# Transmitter_schematic.net
KiCad netlist of a schematic drawn in EasyEDA
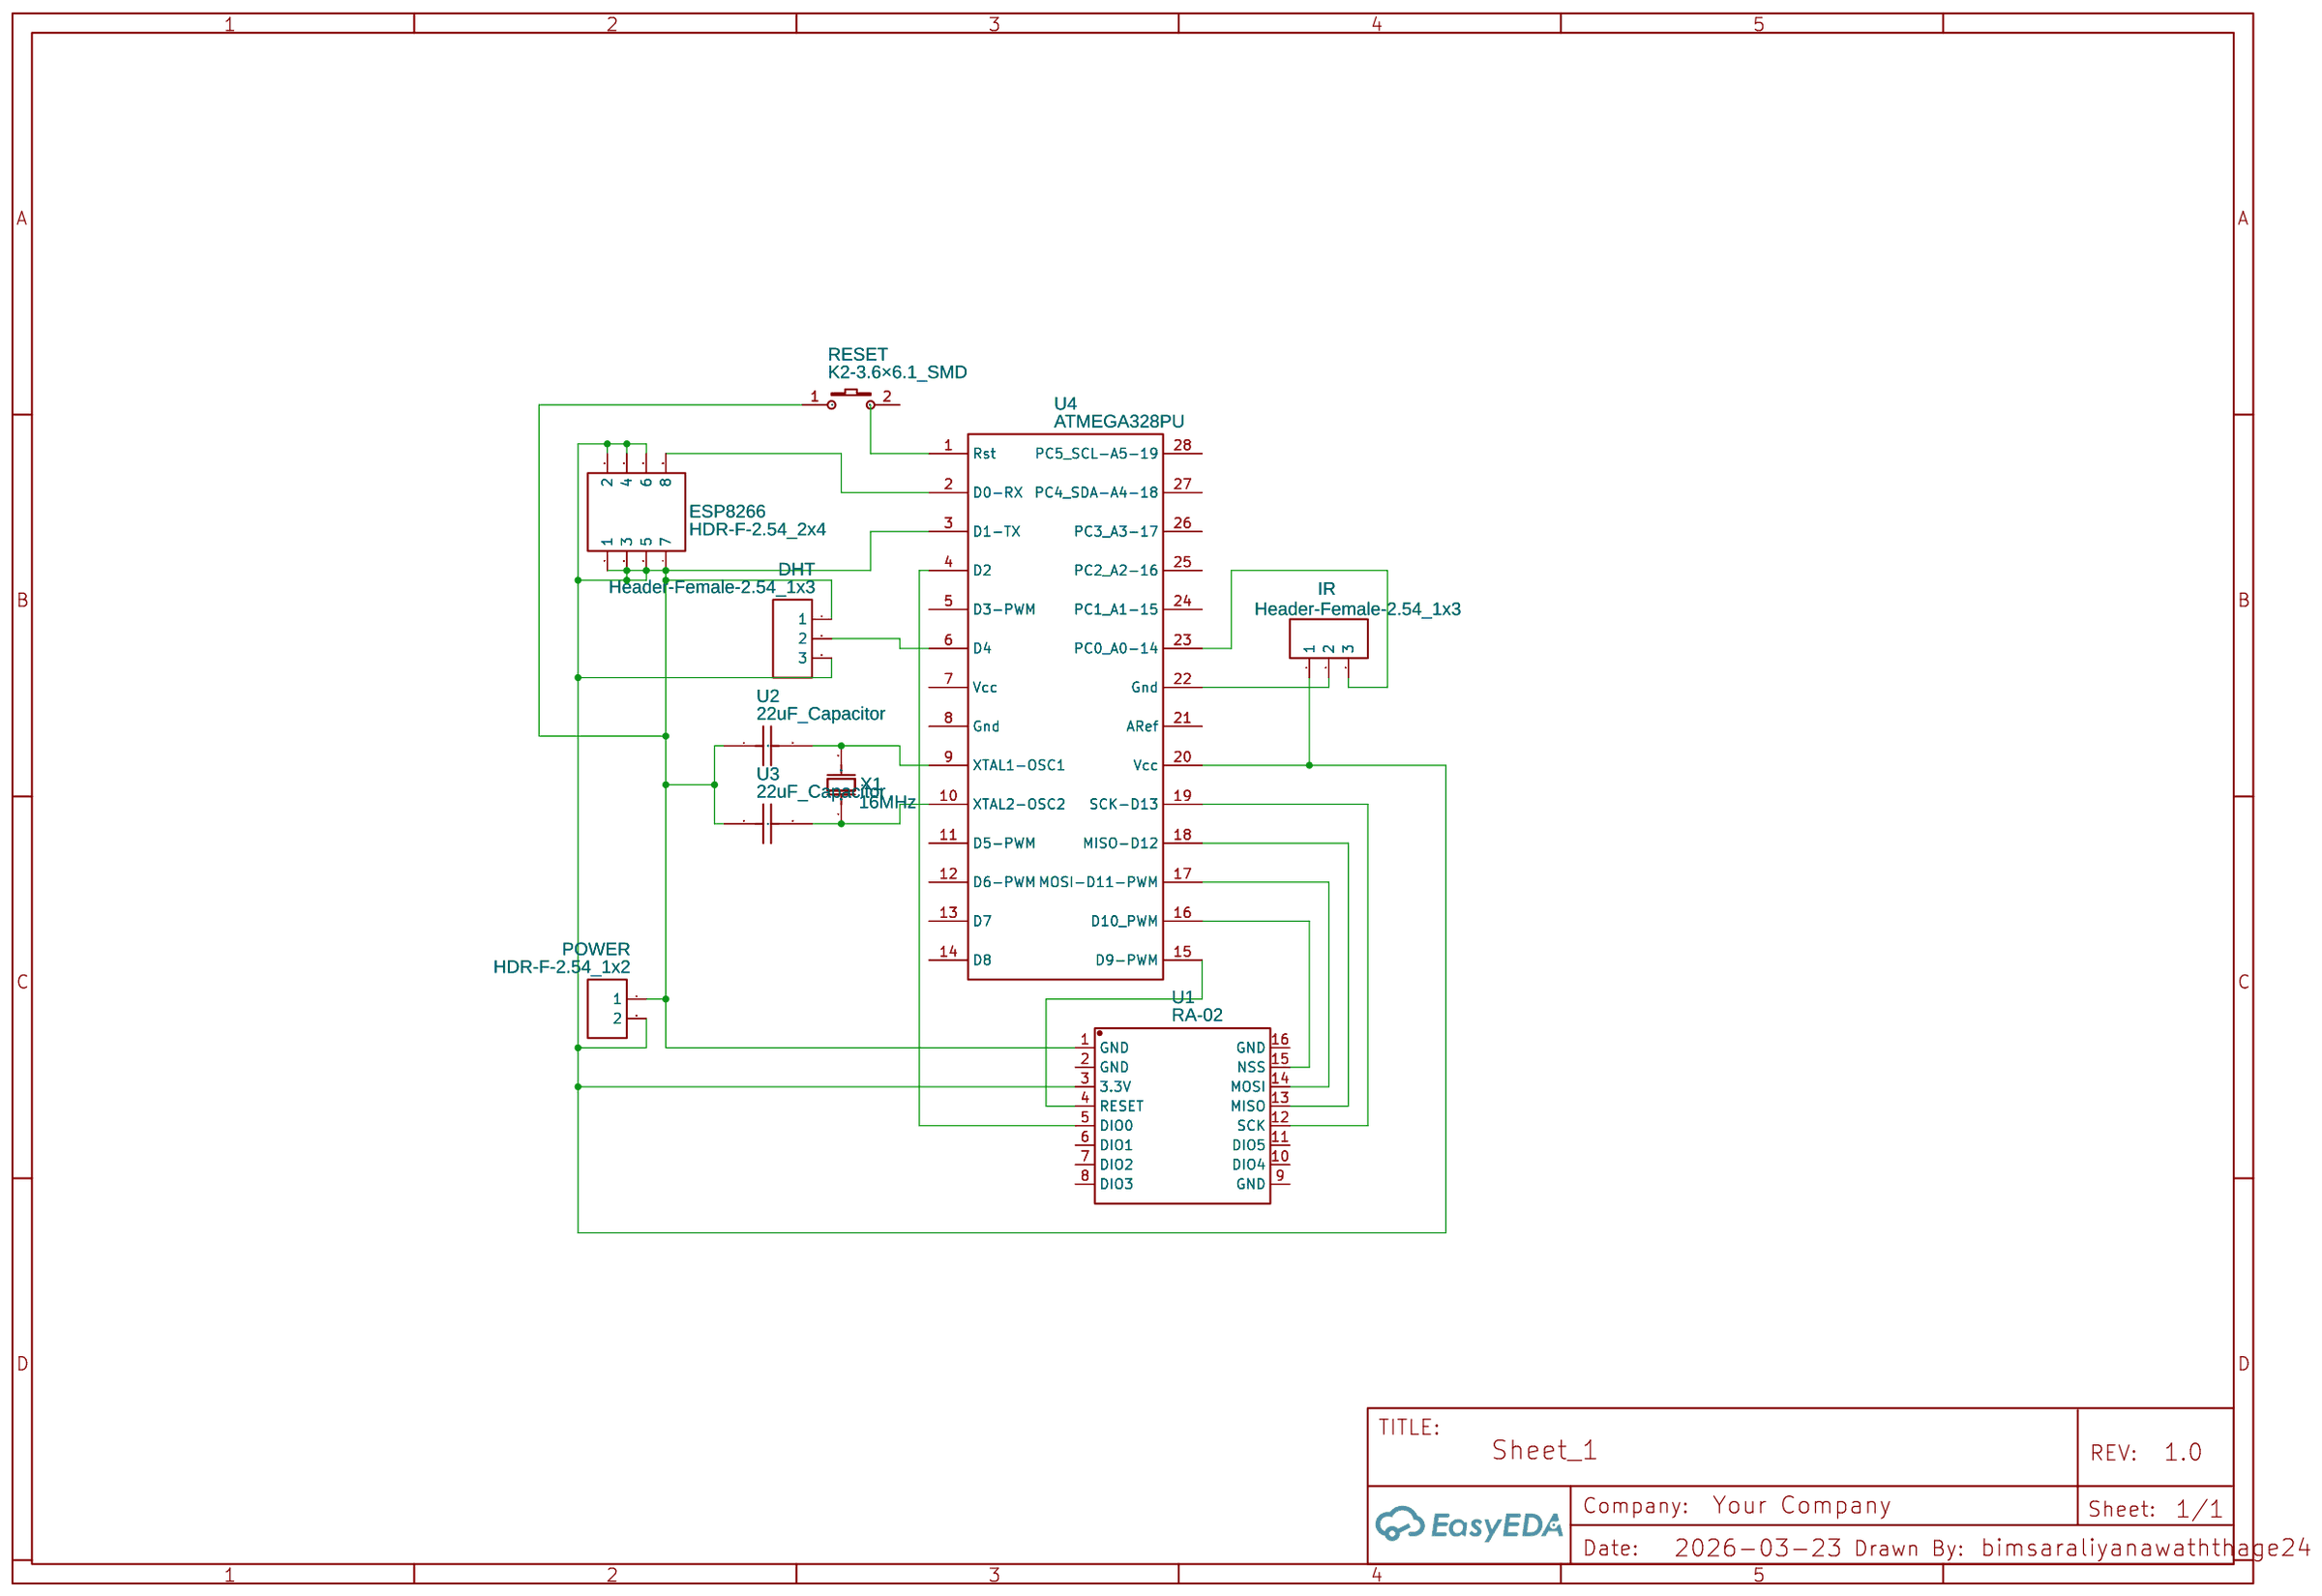
[diagram p0: schematic sheet]

(export (version "E")
  (design (tool "Eeschema 10.0.6"))
  (components
    (comp (ref "DHT")
      (value "Header-Female-2.54_1x3")
      (fields (field (name "Manufacturer Part") "2.54-1*3P母") (field (name "Manufacturer") "BOOMELE(博穆精密)"))
      (libsource (lib "") (part "Header-Female-2.54_1x3"))
    )
    (comp (ref "ESP8266") (value "HDR-F-2.54_2x4") (libsource (lib "") (part "HDR-F-2.54_2x4")))
    (comp (ref "IR")
      (value "Header-Female-2.54_1x3")
      (fields (field (name "Manufacturer Part") "2.54-1*3P母") (field (name "Manufacturer") "BOOMELE(博穆精密)"))
      (libsource (lib "") (part "Header-Female-2.54_1x3_1"))
    )
    (comp (ref "POWER") (value "HDR-F-2.54_1x2") (libsource (lib "") (part "HDR-F-2.54_1x2")))
    (comp (ref "RESET")
      (value "K2-3.6×6.1_SMD")
      (fields (field (name "Manufacturer Part") "K2-1107ST-A4SW-06"))
      (libsource (lib "") (part "K2-3.6×6.1_SMD"))
    )
    (comp (ref "U1")
      (value "RA-02")
      (fields (field (name "Manufacturer Part") "Ra-02") (field (name "Manufacturer") "Ai-Thinker(安信可)"))
      (libsource (lib "") (part "RA-02"))
    )
    (comp (ref "U2") (value "22uF_Capacitor") (libsource (lib "") (part "22uF_Capacitor")))
    (comp (ref "U3") (value "22uF_Capacitor") (libsource (lib "") (part "22uF_Capacitor")))
    (comp (ref "U4") (value "ATMEGA328PU") (libsource (lib "") (part "ATMEGA328PU")))
    (comp (ref "X1")
      (value "16MHz")
      (fields (field (name "Manufacturer Part") "9B-48.000MAAE-B") (field (name "Manufacturer") "TXC"))
      (libsource (lib "") (part "CRISTAL_16MHZ"))
    )
  )
  (nets
    (net (code "1") (name "Net-(IR-Pad2)") (class "Default")
      (node (ref "IR") (pin "2") (pinfunction "2_2") (pintype "input"))
      (node (ref "U4") (pin "22") (pinfunction "Gnd_22") (pintype "unspecified"))
    )
    (net (code "2") (name "Net-(U1-3.3V)") (class "Default")
      (node (ref "DHT") (pin "1") (pinfunction "1_1") (pintype "input"))
      (node (ref "DHT") (pin "3") (pinfunction "3_3") (pintype "input"))
      (node (ref "ESP8266") (pin "1") (pinfunction "1_1") (pintype "unspecified"))
      (node (ref "ESP8266") (pin "2") (pinfunction "2_2") (pintype "unspecified"))
      (node (ref "ESP8266") (pin "3") (pinfunction "3_3") (pintype "unspecified"))
      (node (ref "ESP8266") (pin "4") (pinfunction "4_4") (pintype "unspecified"))
      (node (ref "ESP8266") (pin "5") (pinfunction "5_5") (pintype "unspecified"))
      (node (ref "ESP8266") (pin "6") (pinfunction "6_6") (pintype "unspecified"))
      (node (ref "ESP8266") (pin "7") (pinfunction "7_7") (pintype "unspecified"))
      (node (ref "IR") (pin "1") (pinfunction "1_1") (pintype "input"))
      (node (ref "POWER") (pin "1") (pinfunction "1_1") (pintype "input"))
      (node (ref "POWER") (pin "2") (pinfunction "2_2") (pintype "input"))
      (node (ref "RESET") (pin "1") (pinfunction "1_1") (pintype "unspecified"))
      (node (ref "U1") (pin "1") (pinfunction "GND_1") (pintype "unspecified"))
      (node (ref "U1") (pin "3") (pinfunction "3.3V_3") (pintype "unspecified"))
      (node (ref "U2") (pin "1") (pinfunction "1_1") (pintype "unspecified"))
      (node (ref "U3") (pin "1") (pinfunction "1_1") (pintype "unspecified"))
      (node (ref "U4") (pin "20") (pinfunction "Vcc_20") (pintype "unspecified"))
      (node (ref "U4") (pin "3") (pinfunction "D1-TX_3") (pintype "unspecified"))
    )
    (net (code "3") (name "Net-(U1-DIO0)") (class "Default")
      (node (ref "U1") (pin "5") (pinfunction "DIO0_5") (pintype "unspecified"))
      (node (ref "U4") (pin "4") (pinfunction "D2_4") (pintype "unspecified"))
    )
    (net (code "4") (name "Net-(U1-MISO)") (class "Default")
      (node (ref "U1") (pin "13") (pinfunction "MISO_13") (pintype "unspecified"))
      (node (ref "U4") (pin "18") (pinfunction "MISO-D12_18") (pintype "unspecified"))
    )
    (net (code "5") (name "Net-(U1-MOSI)") (class "Default")
      (node (ref "U1") (pin "14") (pinfunction "MOSI_14") (pintype "unspecified"))
      (node (ref "U4") (pin "17") (pinfunction "MOSI-D11-PWM_17") (pintype "unspecified"))
    )
    (net (code "6") (name "Net-(U1-NSS)") (class "Default")
      (node (ref "U1") (pin "15") (pinfunction "NSS_15") (pintype "unspecified"))
      (node (ref "U4") (pin "16") (pinfunction "D10_PWM_16") (pintype "unspecified"))
    )
    (net (code "7") (name "Net-(U1-RESET)") (class "Default")
      (node (ref "U1") (pin "4") (pinfunction "RESET_4") (pintype "unspecified"))
      (node (ref "U4") (pin "15") (pinfunction "D9-PWM_15") (pintype "unspecified"))
    )
    (net (code "8") (name "Net-(U1-SCK)") (class "Default")
      (node (ref "U1") (pin "12") (pinfunction "SCK_12") (pintype "unspecified"))
      (node (ref "U4") (pin "19") (pinfunction "SCK-D13_19") (pintype "unspecified"))
    )
    (net (code "9") (name "Net-(U4-D0-RX)") (class "Default")
      (node (ref "ESP8266") (pin "8") (pinfunction "8_8") (pintype "unspecified"))
      (node (ref "U4") (pin "2") (pinfunction "D0-RX_2") (pintype "unspecified"))
    )
    (net (code "10") (name "Net-(U4-D4)") (class "Default")
      (node (ref "DHT") (pin "2") (pinfunction "2_2") (pintype "input"))
      (node (ref "U4") (pin "6") (pinfunction "D4_6") (pintype "unspecified"))
    )
    (net (code "11") (name "Net-(U4-PC0_A0-14)") (class "Default")
      (node (ref "IR") (pin "3") (pinfunction "3_3") (pintype "input"))
      (node (ref "U4") (pin "23") (pinfunction "PC0_A0-14_23") (pintype "unspecified"))
    )
    (net (code "12") (name "Net-(U4-XTAL1-OSC1)") (class "Default")
      (node (ref "U2") (pin "2") (pinfunction "2_2") (pintype "unspecified"))
      (node (ref "U4") (pin "9") (pinfunction "XTAL1-OSC1_9") (pintype "unspecified"))
      (node (ref "X1") (pin "2") (pinfunction "OSC2_2") (pintype "unspecified"))
    )
    (net (code "13") (name "Net-(U4-XTAL2-OSC2)") (class "Default")
      (node (ref "U3") (pin "2") (pinfunction "2_2") (pintype "unspecified"))
      (node (ref "U4") (pin "10") (pinfunction "XTAL2-OSC2_10") (pintype "unspecified"))
      (node (ref "X1") (pin "1") (pinfunction "OSC1_1") (pintype "unspecified"))
    )
    (net (code "14") (name "unconnected-(RESET-Pad2)") (class "Default")
      (node (ref "RESET") (pin "2") (pinfunction "2_2") (pintype "unspecified"))
    )
    (net (code "15") (name "unconnected-(U1-DIO1-Pad6)") (class "Default")
      (node (ref "U1") (pin "6") (pinfunction "DIO1_6") (pintype "unspecified"))
    )
    (net (code "16") (name "unconnected-(U1-DIO2-Pad7)") (class "Default")
      (node (ref "U1") (pin "7") (pinfunction "DIO2_7") (pintype "unspecified"))
    )
    (net (code "17") (name "unconnected-(U1-DIO3-Pad8)") (class "Default")
      (node (ref "U1") (pin "8") (pinfunction "DIO3_8") (pintype "unspecified"))
    )
    (net (code "18") (name "unconnected-(U1-DIO4-Pad10)") (class "Default")
      (node (ref "U1") (pin "10") (pinfunction "DIO4_10") (pintype "unspecified"))
    )
    (net (code "19") (name "unconnected-(U1-DIO5-Pad11)") (class "Default")
      (node (ref "U1") (pin "11") (pinfunction "DIO5_11") (pintype "unspecified"))
    )
    (net (code "20") (name "unconnected-(U1-GND-Pad2)") (class "Default")
      (node (ref "U1") (pin "2") (pinfunction "GND_2") (pintype "unspecified"))
    )
    (net (code "21") (name "unconnected-(U1-GND-Pad9)") (class "Default")
      (node (ref "U1") (pin "9") (pinfunction "GND_9") (pintype "unspecified"))
    )
    (net (code "22") (name "unconnected-(U1-GND-Pad16)") (class "Default")
      (node (ref "U1") (pin "16") (pinfunction "GND_16") (pintype "unspecified"))
    )
    (net (code "23") (name "unconnected-(U4-ARef-Pad21)") (class "Default")
      (node (ref "U4") (pin "21") (pinfunction "ARef_21") (pintype "unspecified"))
    )
    (net (code "24") (name "unconnected-(U4-D3-PWM-Pad5)") (class "Default")
      (node (ref "U4") (pin "5") (pinfunction "D3-PWM_5") (pintype "unspecified"))
    )
    (net (code "25") (name "unconnected-(U4-D5-PWM-Pad11)") (class "Default")
      (node (ref "U4") (pin "11") (pinfunction "D5-PWM_11") (pintype "unspecified"))
    )
    (net (code "26") (name "unconnected-(U4-D6-PWM-Pad12)") (class "Default")
      (node (ref "U4") (pin "12") (pinfunction "D6-PWM_12") (pintype "unspecified"))
    )
    (net (code "27") (name "unconnected-(U4-D7-Pad13)") (class "Default")
      (node (ref "U4") (pin "13") (pinfunction "D7_13") (pintype "unspecified"))
    )
    (net (code "28") (name "unconnected-(U4-D8-Pad14)") (class "Default")
      (node (ref "U4") (pin "14") (pinfunction "D8_14") (pintype "unspecified"))
    )
    (net (code "29") (name "unconnected-(U4-Gnd-Pad8)") (class "Default")
      (node (ref "U4") (pin "8") (pinfunction "Gnd_8") (pintype "unspecified"))
    )
    (net (code "30") (name "unconnected-(U4-PC1_A1-15-Pad24)") (class "Default")
      (node (ref "U4") (pin "24") (pinfunction "PC1_A1-15_24") (pintype "unspecified"))
    )
    (net (code "31") (name "unconnected-(U4-PC2_A2-16-Pad25)") (class "Default")
      (node (ref "U4") (pin "25") (pinfunction "PC2_A2-16_25") (pintype "unspecified"))
    )
    (net (code "32") (name "unconnected-(U4-PC3_A3-17-Pad26)") (class "Default")
      (node (ref "U4") (pin "26") (pinfunction "PC3_A3-17_26") (pintype "unspecified"))
    )
    (net (code "33") (name "unconnected-(U4-PC4_SDA-A4-18-Pad27)") (class "Default")
      (node (ref "U4") (pin "27") (pinfunction "PC4_SDA-A4-18_27") (pintype "unspecified"))
    )
    (net (code "34") (name "unconnected-(U4-PC5_SCL-A5-19-Pad28)") (class "Default")
      (node (ref "U4") (pin "28") (pinfunction "PC5_SCL-A5-19_28") (pintype "unspecified"))
    )
    (net (code "35") (name "unconnected-(U4-Rst-Pad1)") (class "Default")
      (node (ref "U4") (pin "1") (pinfunction "Rst_1") (pintype "unspecified"))
    )
    (net (code "36") (name "unconnected-(U4-Vcc-Pad7)") (class "Default")
      (node (ref "U4") (pin "7") (pinfunction "Vcc_7") (pintype "unspecified"))
    )
  )
)
